# BPF.net
KiCad netlist of a schematic drawn in Altium Designer
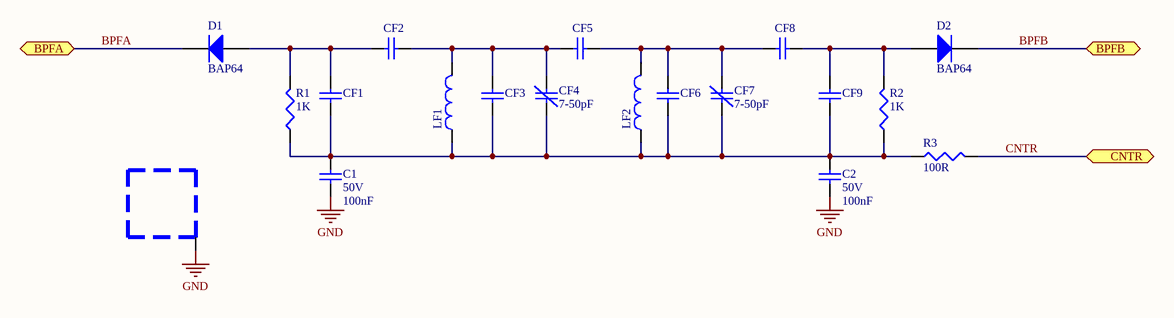
[diagram p0: BPF.SchDoc]

(export (version "E")
  (design (tool "Eeschema 10.0.6"))
  (components
    (comp (ref "BL1")
      (value "Blindagem BPF")
      (footprint "SHIELD_26.5X26.5")
      (libsource (lib "Navarro") (part "Blindagem BPF"))
    )
    (comp (ref "C1")
      (value "100nF")
      (footprint "CC0603")
      (description "Capacitor (Semiconductor SIM Model)")
      (fields (field (name "TENSÃO") "50V") (field (name "Comment") "Capacitor Cerâmico"))
      (libsource (lib "NavarroCAP") (part "Cap 100nF 50V 0603 X7R"))
    )
    (comp (ref "C2")
      (value "100nF")
      (footprint "CC0603")
      (description "Capacitor (Semiconductor SIM Model)")
      (fields (field (name "TENSÃO") "50V") (field (name "Comment") "Capacitor Cerâmico"))
      (libsource (lib "NavarroCAP") (part "Cap 100nF 50V 0603 X7R"))
    )
    (comp (ref "CF1")
      (value "Capacitor Cerâmico")
      (footprint "CC0603")
      (description "Capacitor (Semiconductor SIM Model)")
      (libsource (lib "NavarroCAP") (part "Cap - $Val $V $Footprint $Classe_1"))
    )
    (comp (ref "CF2")
      (value "Capacitor Cerâmico")
      (footprint "CC0603")
      (description "Capacitor (Semiconductor SIM Model)")
      (libsource (lib "NavarroCAP") (part "Cap - $Val $V $Footprint $Classe_1"))
    )
    (comp (ref "CF3")
      (value "Capacitor Cerâmico")
      (footprint "CC0603")
      (description "Capacitor (Semiconductor SIM Model)")
      (libsource (lib "NavarroCAP") (part "Cap - $Val $V $Footprint $Classe_1"))
    )
    (comp (ref "CF4")
      (value "7-50pF")
      (footprint "MURATA TZB4")
      (description "Capacitor (Semiconductor SIM Model)")
      (fields (field (name "Comment") "Trimmer"))
      (libsource (lib "NavarroCAP") (part "Trimmer 7-50pF 50V TZB4-BB"))
    )
    (comp (ref "CF5")
      (value "Capacitor Cerâmico")
      (footprint "CC0603")
      (description "Capacitor (Semiconductor SIM Model)")
      (libsource (lib "NavarroCAP") (part "Cap - $Val $V $Footprint $Classe_1"))
    )
    (comp (ref "CF6")
      (value "Capacitor Cerâmico")
      (footprint "CC0603")
      (description "Capacitor (Semiconductor SIM Model)")
      (libsource (lib "NavarroCAP") (part "Cap - $Val $V $Footprint $Classe_1"))
    )
    (comp (ref "CF7")
      (value "7-50pF")
      (footprint "MURATA TZB4")
      (description "Capacitor (Semiconductor SIM Model)")
      (fields (field (name "Comment") "Trimmer"))
      (libsource (lib "NavarroCAP") (part "Trimmer 7-50pF 50V TZB4-BB"))
    )
    (comp (ref "CF8")
      (value "Capacitor Cerâmico")
      (footprint "CC0603")
      (description "Capacitor (Semiconductor SIM Model)")
      (libsource (lib "NavarroCAP") (part "Cap - $Val $V $Footprint $Classe_1"))
    )
    (comp (ref "CF9")
      (value "Capacitor Cerâmico")
      (footprint "CC0603")
      (description "Capacitor (Semiconductor SIM Model)")
      (libsource (lib "NavarroCAP") (part "Cap - $Val $V $Footprint $Classe_1"))
    )
    (comp (ref "D1")
      (value "BAP64")
      (footprint "SOD523")
      (description "PIN DIODE")
      (libsource (lib "NavarroSEMI") (part "PIN BAP64"))
    )
    (comp (ref "D2")
      (value "BAP64")
      (footprint "SOD523")
      (description "PIN DIODE")
      (libsource (lib "NavarroSEMI") (part "PIN BAP64"))
    )
    (comp (ref "LF1")
      (value "Bead")
      (footprint "CC0603")
      (libsource (lib "NavarroIND") (part "Bd 1K@100MHz 0603 400mA"))
    )
    (comp (ref "LF2")
      (value "Bead")
      (footprint "CC0603")
      (libsource (lib "NavarroIND") (part "Bd 1K@100MHz 0603 400mA"))
    )
    (comp (ref "R1")
      (value "1K")
      (footprint "CC0603")
      (description "Resistor")
      (libsource (lib "NavarroRES") (part "Res 1K 1% 0603 1/10W"))
    )
    (comp (ref "R2")
      (value "1K")
      (footprint "CC0603")
      (description "Resistor")
      (libsource (lib "NavarroRES") (part "Res 1K 1% 0603 1/10W"))
    )
    (comp (ref "R3")
      (value "100R")
      (footprint "CC0603")
      (description "Resistor")
      (libsource (lib "NavarroRES") (part "Res 100R 5% 0603 1/10W"))
    )
  )
  (nets
    (net (code "1") (name "/BPFA") (class "Default")
      (node (ref "D1") (pin "2") (pinfunction "K_2") (pintype "passive"))
    )
    (net (code "2") (name "/BPFB") (class "Default")
      (node (ref "D2") (pin "2") (pinfunction "K_2") (pintype "passive"))
    )
    (net (code "3") (name "/CNTR") (class "Default")
      (node (ref "R3") (pin "2") (pinfunction "2_2") (pintype "passive"))
    )
    (net (code "4") (name "GND") (class "Default")
      (node (ref "BL1") (pin "1") (pinfunction "GND_1") (pintype "power_in"))
      (node (ref "C1") (pin "1") (pinfunction "1_1") (pintype "passive"))
      (node (ref "C2") (pin "1") (pinfunction "1_1") (pintype "passive"))
    )
    (net (code "5") (name "Net-(C1-Pad2)") (class "Default")
      (node (ref "C1") (pin "2") (pinfunction "2_2") (pintype "passive"))
      (node (ref "C2") (pin "2") (pinfunction "2_2") (pintype "passive"))
      (node (ref "CF1") (pin "1") (pinfunction "1_1") (pintype "passive"))
      (node (ref "CF3") (pin "2") (pinfunction "2_2") (pintype "passive"))
      (node (ref "CF4") (pin "1") (pinfunction "1_1") (pintype "passive"))
      (node (ref "CF6") (pin "1") (pinfunction "1_1") (pintype "passive"))
      (node (ref "CF7") (pin "1") (pinfunction "1_1") (pintype "passive"))
      (node (ref "CF9") (pin "2") (pinfunction "2_2") (pintype "passive"))
      (node (ref "LF1") (pin "1") (pinfunction "1_1") (pintype "passive"))
      (node (ref "LF2") (pin "1") (pinfunction "1_1") (pintype "passive"))
      (node (ref "R1") (pin "1") (pinfunction "1_1") (pintype "passive"))
      (node (ref "R2") (pin "1") (pinfunction "1_1") (pintype "passive"))
      (node (ref "R3") (pin "1") (pinfunction "1_1") (pintype "passive"))
    )
    (net (code "6") (name "Net-(CF2-Pad1)") (class "Default")
      (node (ref "CF2") (pin "1") (pinfunction "1_1") (pintype "passive"))
      (node (ref "CF3") (pin "1") (pinfunction "1_1") (pintype "passive"))
      (node (ref "CF4") (pin "2") (pinfunction "2_2") (pintype "passive"))
      (node (ref "CF5") (pin "1") (pinfunction "1_1") (pintype "passive"))
      (node (ref "LF1") (pin "2") (pinfunction "2_2") (pintype "passive"))
    )
    (net (code "7") (name "Net-(CF5-Pad2)") (class "Default")
      (node (ref "CF5") (pin "2") (pinfunction "2_2") (pintype "passive"))
      (node (ref "CF6") (pin "2") (pinfunction "2_2") (pintype "passive"))
      (node (ref "CF7") (pin "2") (pinfunction "2_2") (pintype "passive"))
      (node (ref "CF8") (pin "2") (pinfunction "2_2") (pintype "passive"))
      (node (ref "LF2") (pin "2") (pinfunction "2_2") (pintype "passive"))
    )
    (net (code "8") (name "Net-(D1-A)") (class "Default")
      (node (ref "CF1") (pin "2") (pinfunction "2_2") (pintype "passive"))
      (node (ref "CF2") (pin "2") (pinfunction "2_2") (pintype "passive"))
      (node (ref "D1") (pin "1") (pinfunction "A_1") (pintype "passive"))
      (node (ref "R1") (pin "2") (pinfunction "2_2") (pintype "passive"))
    )
    (net (code "9") (name "Net-(D2-A)") (class "Default")
      (node (ref "CF8") (pin "1") (pinfunction "1_1") (pintype "passive"))
      (node (ref "CF9") (pin "1") (pinfunction "1_1") (pintype "passive"))
      (node (ref "D2") (pin "1") (pinfunction "A_1") (pintype "passive"))
      (node (ref "R2") (pin "2") (pinfunction "2_2") (pintype "passive"))
    )
  )
)
